# oled_game.net
KiCad netlist of a schematic drawn in EAGLE
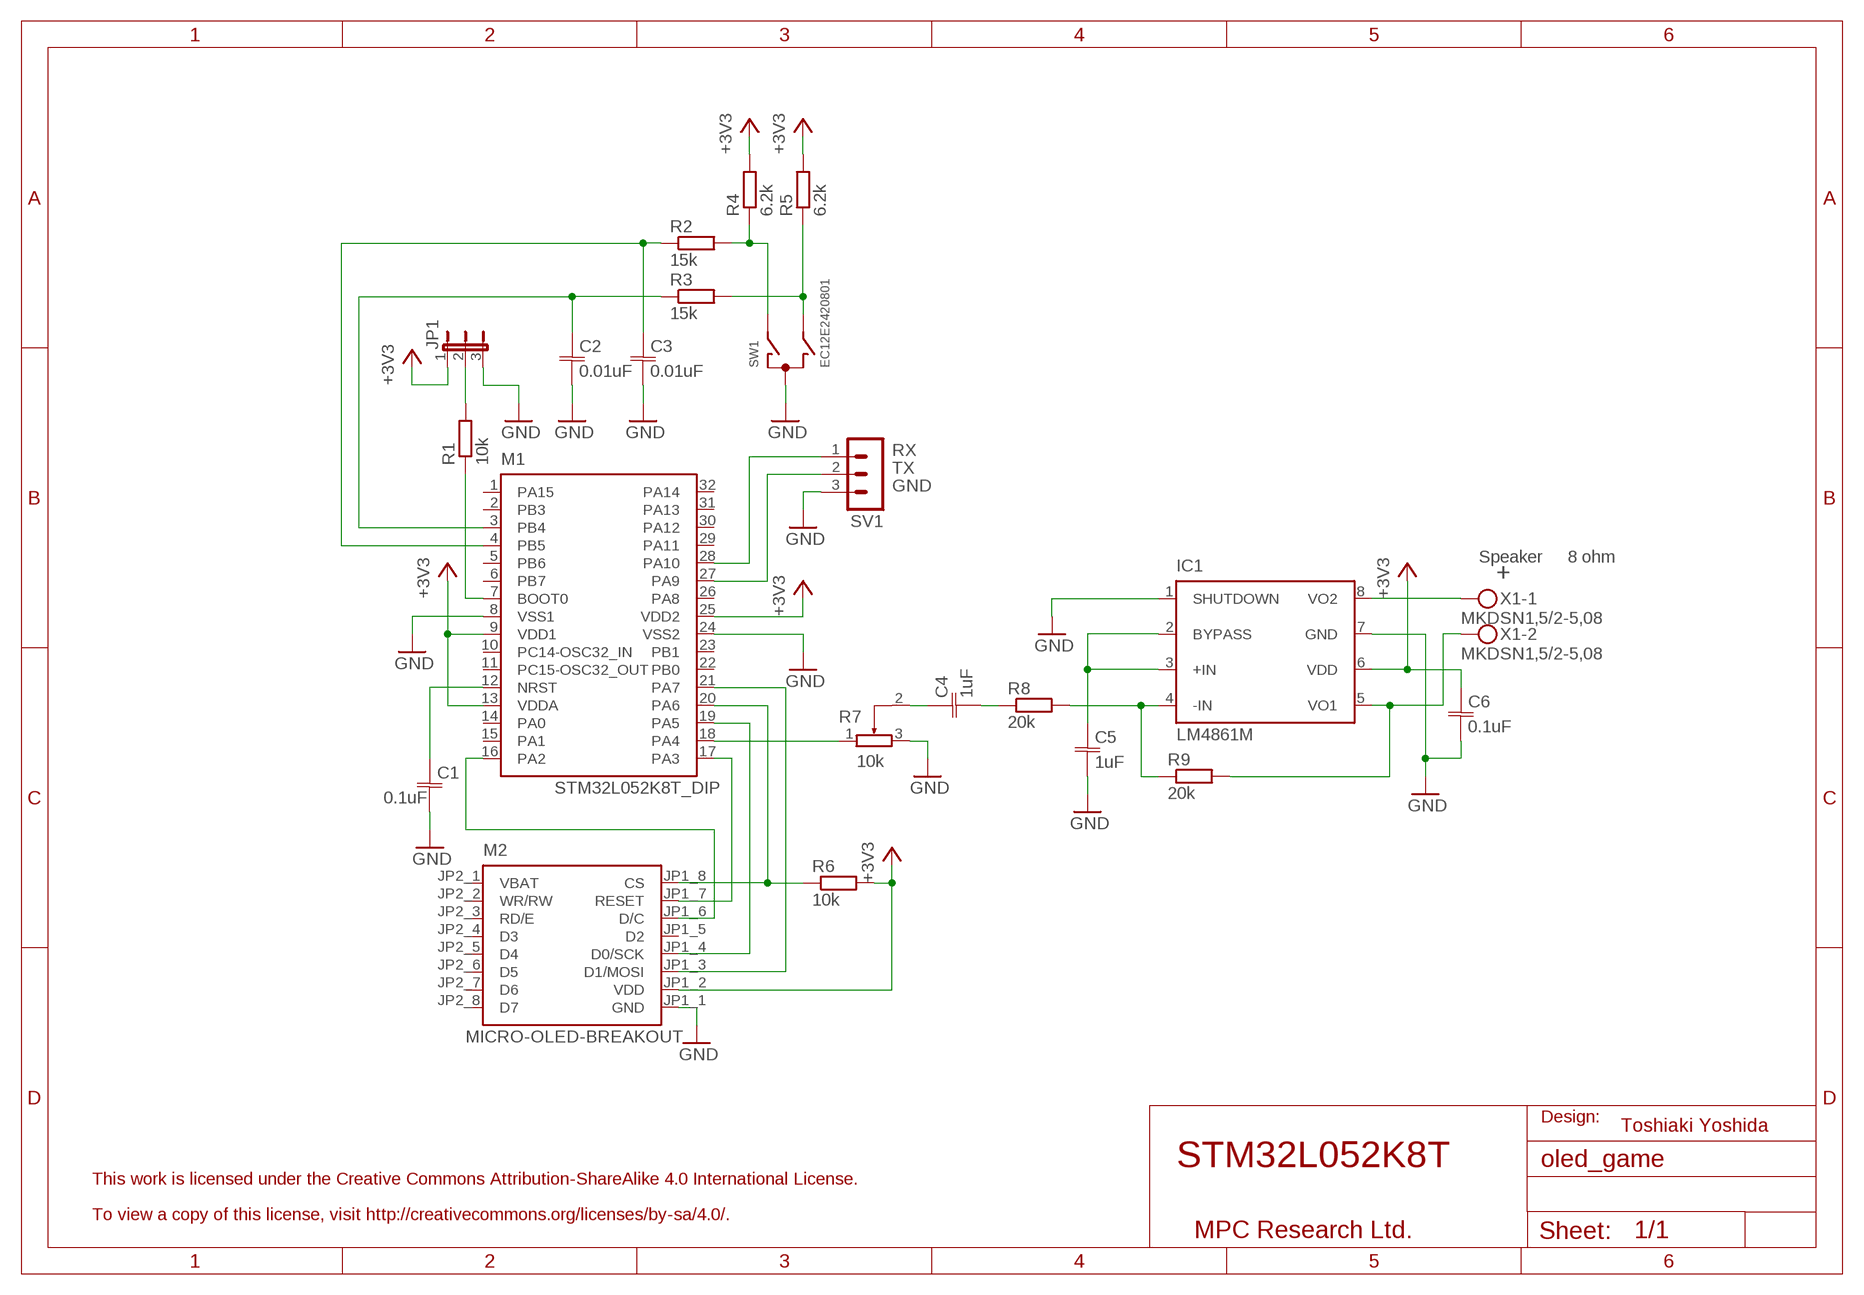
[diagram p0: schematic, sheet 1]

(export (version "E")
  (design (tool "Eeschema 10.0.6"))
  (components
    (comp (ref "C1")
      (value "0.1uF")
      (footprint "eagle-import:C050-024X044")
      (libsource (lib "eagle-import") (part "C-JIS050-024X044"))
    )
    (comp (ref "C2")
      (value "0.01uF")
      (footprint "eagle-import:C050-024X044")
      (libsource (lib "eagle-import") (part "C-JIS050-024X044"))
    )
    (comp (ref "C3")
      (value "0.01uF")
      (footprint "eagle-import:C050-024X044")
      (libsource (lib "eagle-import") (part "C-JIS050-024X044"))
    )
    (comp (ref "C4")
      (value "1uF")
      (footprint "eagle-import:C050-024X044")
      (libsource (lib "eagle-import") (part "C-JIS050-024X044"))
    )
    (comp (ref "C5")
      (value "1uF")
      (footprint "eagle-import:C050-024X044")
      (libsource (lib "eagle-import") (part "C-JIS050-024X044"))
    )
    (comp (ref "C6")
      (value "0.1uF")
      (footprint "eagle-import:C050-024X044")
      (libsource (lib "eagle-import") (part "C-JIS050-024X044"))
    )
    (comp (ref "IC1")
      (value "LM4861M")
      (footprint "eagle-import:SO-08")
      (libsource (lib "eagle-import") (part "LM4861M"))
    )
    (comp (ref "JP1")
      (value "JP2E")
      (footprint "eagle-import:JP2")
      (libsource (lib "eagle-import") (part "JP2E"))
    )
    (comp (ref "M1")
      (value "STM32L052K8T_DIP")
      (footprint "eagle-import:DIP32")
      (libsource (lib "eagle-import") (part "STM32L052K8T_DIP"))
    )
    (comp (ref "M2")
      (value "MICRO-OLED-BREAKOUT")
      (footprint "eagle-import:MICRO-OLED-BREAKOUT")
      (libsource (lib "eagle-import") (part "MICRO-OLED-BREAKOUT"))
    )
    (comp (ref "R1")
      (value "10k")
      (footprint "eagle-import:0207_2V")
      (libsource (lib "eagle-import") (part "R-EU_0207/2V"))
    )
    (comp (ref "R2")
      (value "15k")
      (footprint "eagle-import:0207_2V")
      (libsource (lib "eagle-import") (part "R-EU_0207/2V"))
    )
    (comp (ref "R3")
      (value "15k")
      (footprint "eagle-import:0207_2V")
      (libsource (lib "eagle-import") (part "R-EU_0207/2V"))
    )
    (comp (ref "R4")
      (value "6.2k")
      (footprint "eagle-import:0207_2V")
      (libsource (lib "eagle-import") (part "R-EU_0207/2V"))
    )
    (comp (ref "R5")
      (value "6.2k")
      (footprint "eagle-import:0207_2V")
      (libsource (lib "eagle-import") (part "R-EU_0207/2V"))
    )
    (comp (ref "R6")
      (value "10k")
      (footprint "eagle-import:0207_2V")
      (libsource (lib "eagle-import") (part "R-EU_0207/2V"))
    )
    (comp (ref "R7")
      (value "10k")
      (footprint "eagle-import:TSR-3386T")
      (libsource (lib "eagle-import") (part "TSR-3386T-EY5"))
    )
    (comp (ref "R8")
      (value "20k")
      (footprint "eagle-import:0207_2V")
      (libsource (lib "eagle-import") (part "R-EU_0207/2V"))
    )
    (comp (ref "R9")
      (value "20k")
      (footprint "eagle-import:0207_10")
      (libsource (lib "eagle-import") (part "R-EU_0207/10"))
    )
    (comp (ref "SV1")
      (value "MA03-1")
      (footprint "eagle-import:MA03-1")
      (libsource (lib "eagle-import") (part "MA03-1"))
    )
    (comp (ref "SW1")
      (value "EC12E2420801")
      (footprint "eagle-import:ALPS_EC12E_SW")
      (fields (field (name "MPN") "EC12E2424407"))
      (libsource (lib "eagle-import") (part "EC12E_SW"))
    )
    (comp (ref "X1")
      (value "MKDSN1,5/2-5,08")
      (footprint "eagle-import:MKDSN1,5_2-5,08")
      (libsource (lib "eagle-import") (part "MKDSN1,5/2-5,08"))
    )
  )
  (nets
    (net (code "1") (name "+3V3") (class "Default")
      (node (ref "C6") (pin "1") (pinfunction "1_1") (pintype "passive"))
      (node (ref "IC1") (pin "6") (pinfunction "VDD_6") (pintype "power_in"))
      (node (ref "JP1") (pin "1") (pinfunction "1_1") (pintype "passive"))
      (node (ref "M1") (pin "13") (pinfunction "VDDA_13") (pintype "power_in"))
      (node (ref "M1") (pin "25") (pinfunction "VDD2_25") (pintype "bidirectional"))
      (node (ref "M1") (pin "9") (pinfunction "VDD1_9") (pintype "power_in"))
      (node (ref "M2") (pin "JP1_2") (pinfunction "VDD_JP1_2") (pintype "power_in"))
      (node (ref "R4") (pin "2") (pinfunction "2_2") (pintype "passive"))
      (node (ref "R5") (pin "2") (pinfunction "2_2") (pintype "passive"))
      (node (ref "R6") (pin "2") (pinfunction "2_2") (pintype "passive"))
    )
    (net (code "2") (name "/VBAT") (class "Default")
      (node (ref "M2") (pin "JP2_1") (pinfunction "VBAT_JP2_1") (pintype "power_in"))
    )
    (net (code "3") (name "GND") (class "Default")
      (node (ref "C1") (pin "2") (pinfunction "2_2") (pintype "passive"))
      (node (ref "C2") (pin "2") (pinfunction "2_2") (pintype "passive"))
      (node (ref "C3") (pin "2") (pinfunction "2_2") (pintype "passive"))
      (node (ref "C5") (pin "2") (pinfunction "2_2") (pintype "passive"))
      (node (ref "C6") (pin "2") (pinfunction "2_2") (pintype "passive"))
      (node (ref "IC1") (pin "1") (pinfunction "SHUTDOWN_1") (pintype "input"))
      (node (ref "IC1") (pin "7") (pinfunction "GND_7") (pintype "power_in"))
      (node (ref "JP1") (pin "3") (pinfunction "3_3") (pintype "passive"))
      (node (ref "M1") (pin "24") (pinfunction "VSS2_24") (pintype "power_in"))
      (node (ref "M1") (pin "8") (pinfunction "VSS1_8") (pintype "power_in"))
      (node (ref "M2") (pin "JP1_1") (pinfunction "GND_JP1_1") (pintype "power_in"))
      (node (ref "R7") (pin "3") (pinfunction "3_3") (pintype "passive"))
      (node (ref "SV1") (pin "3") (pinfunction "3_3") (pintype "passive"))
      (node (ref "SW1") (pin "C") (pinfunction "C_C") (pintype "passive"))
    )
    (net (code "4") (name "Net-(C4-Pad1)") (class "Default")
      (node (ref "C4") (pin "1") (pinfunction "1_1") (pintype "passive"))
      (node (ref "R7") (pin "2") (pinfunction "2_2") (pintype "passive"))
    )
    (net (code "5") (name "Net-(C4-Pad2)") (class "Default")
      (node (ref "C4") (pin "2") (pinfunction "2_2") (pintype "passive"))
      (node (ref "R8") (pin "1") (pinfunction "1_1") (pintype "passive"))
    )
    (net (code "6") (name "Net-(IC1-+IN)") (class "Default")
      (node (ref "C5") (pin "1") (pinfunction "1_1") (pintype "passive"))
      (node (ref "IC1") (pin "2") (pinfunction "BYPASS_2") (pintype "passive"))
      (node (ref "IC1") (pin "3") (pinfunction "+IN_3") (pintype "input"))
    )
    (net (code "7") (name "Net-(IC1--IN)") (class "Default")
      (node (ref "IC1") (pin "4") (pinfunction "-IN_4") (pintype "input"))
      (node (ref "R8") (pin "2") (pinfunction "2_2") (pintype "passive"))
      (node (ref "R9") (pin "1") (pinfunction "1_1") (pintype "passive"))
    )
    (net (code "8") (name "Net-(IC1-VO1)") (class "Default")
      (node (ref "IC1") (pin "5") (pinfunction "VO1_5") (pintype "output"))
      (node (ref "R9") (pin "2") (pinfunction "2_2") (pintype "passive"))
      (node (ref "X1") (pin "2") (pinfunction "KL_2") (pintype "passive"))
    )
    (net (code "9") (name "Net-(IC1-VO2)") (class "Default")
      (node (ref "IC1") (pin "8") (pinfunction "VO2_8") (pintype "output"))
      (node (ref "X1") (pin "1") (pinfunction "KL_1") (pintype "passive"))
    )
    (net (code "10") (name "Net-(JP1-Pad2)") (class "Default")
      (node (ref "JP1") (pin "2") (pinfunction "2_2") (pintype "passive"))
      (node (ref "R1") (pin "2") (pinfunction "2_2") (pintype "passive"))
    )
    (net (code "11") (name "Net-(M1-BOOT0)") (class "Default")
      (node (ref "M1") (pin "7") (pinfunction "BOOT0_7") (pintype "bidirectional"))
      (node (ref "R1") (pin "1") (pinfunction "1_1") (pintype "passive"))
    )
    (net (code "12") (name "Net-(M1-NRST)") (class "Default")
      (node (ref "C1") (pin "1") (pinfunction "1_1") (pintype "passive"))
      (node (ref "M1") (pin "12") (pinfunction "NRST_12") (pintype "bidirectional"))
    )
    (net (code "13") (name "Net-(M1-PA2)") (class "Default")
      (node (ref "M1") (pin "16") (pinfunction "PA2_16") (pintype "bidirectional"))
      (node (ref "M2") (pin "JP1_6") (pinfunction "D/C_JP1_6") (pintype "bidirectional"))
    )
    (net (code "14") (name "Net-(M1-PA3)") (class "Default")
      (node (ref "M1") (pin "17") (pinfunction "PA3_17") (pintype "bidirectional"))
      (node (ref "M2") (pin "JP1_7") (pinfunction "RESET_JP1_7") (pintype "input"))
    )
    (net (code "15") (name "Net-(M1-PA4)") (class "Default")
      (node (ref "M1") (pin "18") (pinfunction "PA4_18") (pintype "bidirectional"))
      (node (ref "R7") (pin "1") (pinfunction "1_1") (pintype "passive"))
    )
    (net (code "16") (name "Net-(M1-PA5)") (class "Default")
      (node (ref "M1") (pin "19") (pinfunction "PA5_19") (pintype "bidirectional"))
      (node (ref "M2") (pin "JP1_4") (pinfunction "D0/SCK_JP1_4") (pintype "bidirectional"))
    )
    (net (code "17") (name "Net-(M1-PA6)") (class "Default")
      (node (ref "M1") (pin "20") (pinfunction "PA6_20") (pintype "bidirectional"))
      (node (ref "M2") (pin "JP1_8") (pinfunction "CS_JP1_8") (pintype "input"))
      (node (ref "R6") (pin "1") (pinfunction "1_1") (pintype "passive"))
    )
    (net (code "18") (name "Net-(M1-PA7)") (class "Default")
      (node (ref "M1") (pin "21") (pinfunction "PA7_21") (pintype "bidirectional"))
      (node (ref "M2") (pin "JP1_3") (pinfunction "D1/MOSI_JP1_3") (pintype "bidirectional"))
    )
    (net (code "19") (name "Net-(M1-PA9)") (class "Default")
      (node (ref "M1") (pin "27") (pinfunction "PA9_27") (pintype "bidirectional"))
      (node (ref "SV1") (pin "2") (pinfunction "2_2") (pintype "passive"))
    )
    (net (code "20") (name "Net-(M1-PA10)") (class "Default")
      (node (ref "M1") (pin "28") (pinfunction "PA10_28") (pintype "bidirectional"))
      (node (ref "SV1") (pin "1") (pinfunction "1_1") (pintype "passive"))
    )
    (net (code "21") (name "Net-(M1-PB4)") (class "Default")
      (node (ref "C2") (pin "1") (pinfunction "1_1") (pintype "passive"))
      (node (ref "M1") (pin "3") (pinfunction "PB4_3") (pintype "bidirectional"))
      (node (ref "R3") (pin "1") (pinfunction "1_1") (pintype "passive"))
    )
    (net (code "22") (name "Net-(M1-PB5)") (class "Default")
      (node (ref "C3") (pin "1") (pinfunction "1_1") (pintype "passive"))
      (node (ref "M1") (pin "4") (pinfunction "PB5_4") (pintype "bidirectional"))
      (node (ref "R2") (pin "1") (pinfunction "1_1") (pintype "passive"))
    )
    (net (code "23") (name "Net-(R2-Pad2)") (class "Default")
      (node (ref "R2") (pin "2") (pinfunction "2_2") (pintype "passive"))
      (node (ref "R4") (pin "1") (pinfunction "1_1") (pintype "passive"))
      (node (ref "SW1") (pin "A") (pinfunction "A_A") (pintype "passive"))
    )
    (net (code "24") (name "Net-(R3-Pad2)") (class "Default")
      (node (ref "R3") (pin "2") (pinfunction "2_2") (pintype "passive"))
      (node (ref "R5") (pin "1") (pinfunction "1_1") (pintype "passive"))
      (node (ref "SW1") (pin "B") (pinfunction "B_B") (pintype "passive"))
    )
    (net (code "25") (name "unconnected-(M1-PA0-Pad14)") (class "Default")
      (node (ref "M1") (pin "14") (pinfunction "PA0_14") (pintype "bidirectional"))
    )
    (net (code "26") (name "unconnected-(M1-PA1-Pad15)") (class "Default")
      (node (ref "M1") (pin "15") (pinfunction "PA1_15") (pintype "bidirectional"))
    )
    (net (code "27") (name "unconnected-(M1-PA8-Pad26)") (class "Default")
      (node (ref "M1") (pin "26") (pinfunction "PA8_26") (pintype "bidirectional"))
    )
    (net (code "28") (name "unconnected-(M1-PA11-Pad29)") (class "Default")
      (node (ref "M1") (pin "29") (pinfunction "PA11_29") (pintype "bidirectional"))
    )
    (net (code "29") (name "unconnected-(M1-PA12-Pad30)") (class "Default")
      (node (ref "M1") (pin "30") (pinfunction "PA12_30") (pintype "bidirectional"))
    )
    (net (code "30") (name "unconnected-(M1-PA13-Pad31)") (class "Default")
      (node (ref "M1") (pin "31") (pinfunction "PA13_31") (pintype "bidirectional"))
    )
    (net (code "31") (name "unconnected-(M1-PA14-Pad32)") (class "Default")
      (node (ref "M1") (pin "32") (pinfunction "PA14_32") (pintype "bidirectional"))
    )
    (net (code "32") (name "unconnected-(M1-PA15-Pad1)") (class "Default")
      (node (ref "M1") (pin "1") (pinfunction "PA15_1") (pintype "bidirectional"))
    )
    (net (code "33") (name "unconnected-(M1-PB0-Pad22)") (class "Default")
      (node (ref "M1") (pin "22") (pinfunction "PB0_22") (pintype "bidirectional"))
    )
    (net (code "34") (name "unconnected-(M1-PB1-Pad23)") (class "Default")
      (node (ref "M1") (pin "23") (pinfunction "PB1_23") (pintype "bidirectional"))
    )
    (net (code "35") (name "unconnected-(M1-PB3-Pad2)") (class "Default")
      (node (ref "M1") (pin "2") (pinfunction "PB3_2") (pintype "bidirectional"))
    )
    (net (code "36") (name "unconnected-(M1-PB6-Pad5)") (class "Default")
      (node (ref "M1") (pin "5") (pinfunction "PB6_5") (pintype "bidirectional"))
    )
    (net (code "37") (name "unconnected-(M1-PB7-Pad6)") (class "Default")
      (node (ref "M1") (pin "6") (pinfunction "PB7_6") (pintype "bidirectional"))
    )
    (net (code "38") (name "unconnected-(M1-PC14-OSC32_IN-Pad10)") (class "Default")
      (node (ref "M1") (pin "10") (pinfunction "PC14-OSC32_IN_10") (pintype "bidirectional"))
    )
    (net (code "39") (name "unconnected-(M1-PC15-OSC32_OUT-Pad11)") (class "Default")
      (node (ref "M1") (pin "11") (pinfunction "PC15-OSC32_OUT_11") (pintype "bidirectional"))
    )
    (net (code "40") (name "unconnected-(M2-D2-PadJP1_5)") (class "Default")
      (node (ref "M2") (pin "JP1_5") (pinfunction "D2_JP1_5") (pintype "bidirectional"))
    )
    (net (code "41") (name "unconnected-(M2-D3-PadJP2_4)") (class "Default")
      (node (ref "M2") (pin "JP2_4") (pinfunction "D3_JP2_4") (pintype "bidirectional"))
    )
    (net (code "42") (name "unconnected-(M2-D4-PadJP2_5)") (class "Default")
      (node (ref "M2") (pin "JP2_5") (pinfunction "D4_JP2_5") (pintype "bidirectional"))
    )
    (net (code "43") (name "unconnected-(M2-D5-PadJP2_6)") (class "Default")
      (node (ref "M2") (pin "JP2_6") (pinfunction "D5_JP2_6") (pintype "bidirectional"))
    )
    (net (code "44") (name "unconnected-(M2-D6-PadJP2_7)") (class "Default")
      (node (ref "M2") (pin "JP2_7") (pinfunction "D6_JP2_7") (pintype "bidirectional"))
    )
    (net (code "45") (name "unconnected-(M2-D7-PadJP2_8)") (class "Default")
      (node (ref "M2") (pin "JP2_8") (pinfunction "D7_JP2_8") (pintype "bidirectional"))
    )
    (net (code "46") (name "unconnected-(M2-RD{slash}E-PadJP2_3)") (class "Default")
      (node (ref "M2") (pin "JP2_3") (pinfunction "RD/E_JP2_3") (pintype "input"))
    )
    (net (code "47") (name "unconnected-(M2-WR{slash}RW-PadJP2_2)") (class "Default")
      (node (ref "M2") (pin "JP2_2") (pinfunction "WR/RW_JP2_2") (pintype "input"))
    )
  )
)
